# design.net
KiCad netlist of a schematic drawn in Altium Designer
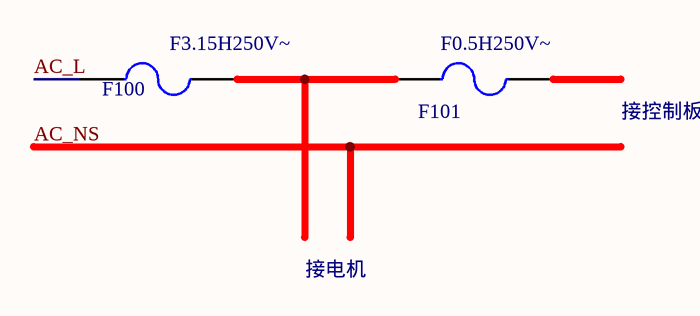
[diagram p0: 保险丝作图.SchDoc]

(export (version "E")
  (design (tool "Eeschema 10.0.6"))
  (components
    (comp (ref "F100")
      (value "F3.15H250V~")
      (footprint "FUSE21.5*5.4-H-30")
      (fields (field (name "PUBLISHER") "Altium Limited"))
      (libsource (lib "Miscellaneous Devices") (part "Fuse 2"))
    )
    (comp (ref "F101")
      (value "F0.5H250V~")
      (footprint "FUSE21.5*5.4-H-30")
      (fields (field (name "PUBLISHER") "Altium Limited"))
      (libsource (lib "Miscellaneous Devices") (part "Fuse 2"))
    )
  )
  (nets
    (net (code "1") (name "/AC_L") (class "Default")
      (node (ref "F100") (pin "1") (pinfunction "1_1") (pintype "passive"))
    )
    (net (code "3") (name "Net-(F100-Pad2)") (class "Default")
      (node (ref "F100") (pin "2") (pinfunction "2_2") (pintype "passive"))
      (node (ref "F101") (pin "1") (pinfunction "1_1") (pintype "passive"))
    )
    (net (code "4") (name "unconnected-(F101-Pad2)") (class "Default")
      (node (ref "F101") (pin "2") (pinfunction "2_2") (pintype "passive"))
    )
  )
)
